# Buzzer_Circuit.net
KiCad netlist of a schematic drawn in Altium Designer
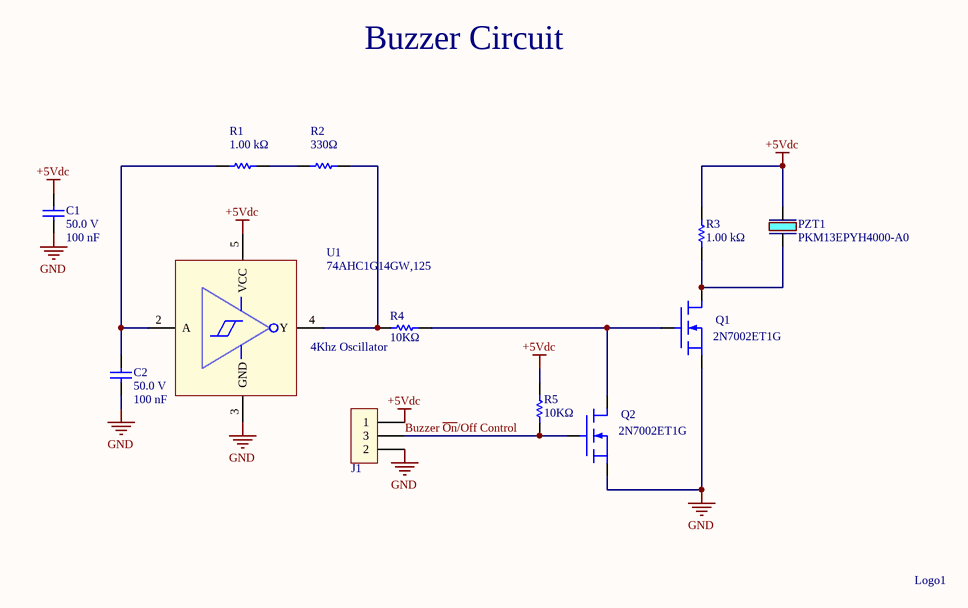
[diagram p0: Buzzer Circuit.SchDoc]

(export (version "E")
  (design (tool "Eeschema 10.0.6"))
  (components
    (comp (ref "C1")
      (value "08055C104JAT2A")
      (footprint "Cap,0805")
      (description "Capacitor; Ceramic; Cap 0.1 uF; Tol 5%; Vol-Rtg 50 VDC; SMT; 0805; X7R; Tape & Reel")
      (fields (field (name "VOLTAGE RATING (DC)") "50.0 V") (field (name "CAPACITANCE") "100 nF"))
      (libsource (lib "Master Mar2021") (part "Cap,0805,100nf,50V,5%,08055C104JAT2A"))
    )
    (comp (ref "C2")
      (value "08055C104JAT2A")
      (footprint "Cap,0805")
      (description "Capacitor; Ceramic; Cap 0.1 uF; Tol 5%; Vol-Rtg 50 VDC; SMT; 0805; X7R; Tape & Reel")
      (fields (field (name "VOLTAGE RATING (DC)") "50.0 V") (field (name "CAPACITANCE") "100 nF"))
      (libsource (lib "Master Mar2021") (part "Cap,0805,100nf,50V,5%,08055C104JAT2A"))
    )
    (comp (ref "J1")
      (value "Generic Header")
      (footprint "Header,3POS,0.1\",RA")
      (description "Generic Header 3 pos header 0.1\"")
      (libsource (lib "Master DEC 2020") (part "Header 1x3,0.1{dblquote},TH,Generic"))
    )
    (comp (ref "Logo1")
      (value "Open Source Logo")
      (footprint "Symbol,Open Source")
      (description "Open Source Silk Screen Logo")
      (libsource (lib "Master Mar2024") (part "Symbol,Open Source"))
    )
    (comp (ref "PZT1")
      (value "PKM13EPYH4000-A0")
      (footprint "Buzzer,PKM13EPYH4000-A0")
      (description "AUDIO PIEZO TRANSDUCER 30V TH")
      (fields (field (name "MANUFACTURER") "Murata Electronics"))
      (libsource (lib "Master Mar2021") (part "Buzzer,PIEZO,30V,TH,4Khz,PKM13EPYH4000-A0"))
    )
    (comp (ref "Q1")
      (value "2N7002ET1G")
      (footprint "SOT23-3")
      (description "Small Signal MOSFET, 60 V, 310 mA, Single, N-Channel, 3-Pin SOT-23, Pb-Free, Tape and Reel")
      (fields
        (field (name "MANUFACTURER") "ON Semiconductor")
        (field (name "MANUFACTURER PART NUMBER") "2N7002ET1G")
      )
      (libsource (lib "Master Mar2021") (part "MOSFET,N-Channel,SOT23,0.25A,60V,2N7002ET1G"))
    )
    (comp (ref "Q2")
      (value "2N7002ET1G")
      (footprint "SOT23-3")
      (description "Small Signal MOSFET, 60 V, 310 mA, Single, N-Channel, 3-Pin SOT-23, Pb-Free, Tape and Reel")
      (fields
        (field (name "MANUFACTURER") "ON Semiconductor")
        (field (name "MANUFACTURER PART NUMBER") "2N7002ET1G")
      )
      (libsource (lib "Master Mar2021") (part "MOSFET,N-Channel,SOT23,0.25A,60V,2N7002ET1G"))
    )
    (comp (ref "R1")
      (value "Vishay CRCW08051K00JNEA")
      (footprint "res, 0805, HD")
      (description "Res Thick Film 0805 1K Ohm 5% 0.125W(1/8W) ±200ppm/C Molded SMD Automotive Paper T/R")
      (fields
        (field (name "MANUFACTURER PART NUMBER") "CRCW08051K00JNEA")
        (field (name "RESISTANCE") "1.00 kΩ")
      )
      (libsource (lib "Master Mar2021") (part "Res,0805,1.00 kΩ,5%,200ppm,CRCW08051K00JNEA"))
    )
    (comp (ref "R2")
      (value "Res1")
      (footprint "res, 0805, HD")
      (fields (field (name "RESISTANCE") "330Ω"))
      (libsource (lib "Master Nov2021") (part "Res,0805,Generic"))
    )
    (comp (ref "R3")
      (value "Vishay CRCW08051K00JNEA")
      (footprint "res, 0805, HD")
      (description "Res Thick Film 0805 1K Ohm 5% 0.125W(1/8W) ±200ppm/C Molded SMD Automotive Paper T/R")
      (fields
        (field (name "MANUFACTURER PART NUMBER") "CRCW08051K00JNEA")
        (field (name "RESISTANCE") "1.00 kΩ")
      )
      (libsource (lib "Master Mar2021") (part "Res,0805,1.00 kΩ,5%,200ppm,CRCW08051K00JNEA"))
    )
    (comp (ref "R4")
      (value "Vishay / Dale CRCW080510K0FKTA")
      (footprint "res, 0805, HD")
      (description "RES SMD 10K OHM 1% 1/8W 0805")
      (fields (field (name "RESISTANCE") "10KΩ"))
      (libsource (lib "Master Mar2021") (part "Res,0805,10.0kΩ,1%,100 ppm,CRCW080510K0FKTA"))
    )
    (comp (ref "R5")
      (value "Vishay / Dale CRCW080510K0FKTA")
      (footprint "res, 0805, HD")
      (description "RES SMD 10K OHM 1% 1/8W 0805")
      (fields (field (name "RESISTANCE") "10KΩ"))
      (libsource (lib "Master Mar2021") (part "Res,0805,10.0kΩ,1%,100 ppm,CRCW080510K0FKTA"))
    )
    (comp (ref "U1")
      (value "74AHC1G14GW,125")
      (footprint "SOT-353")
      (description "IC INVERTER SCHMITT 1CH 5TSSOP")
      (fields (field (name "MANUFACTURER") "Nexperia USA Inc."))
      (libsource (lib "Master Nov2021") (part "IC,Logic,Schmitt trigger INV,2V ~ 5.5V,5-TSSOP , 74AHC1G14GW,125"))
    )
  )
  (nets
    (net (code "1") (name "+5Vdc") (class "Default")
      (node (ref "C1") (pin "2") (pinfunction "2_2") (pintype "passive"))
      (node (ref "J1") (pin "1") (pinfunction "1_1") (pintype "passive"))
      (node (ref "PZT1") (pin "2") (pinfunction "2_2") (pintype "passive"))
      (node (ref "R3") (pin "1") (pinfunction "1_1") (pintype "passive"))
      (node (ref "R5") (pin "1") (pinfunction "1_1") (pintype "passive"))
      (node (ref "U1") (pin "5") (pinfunction "VCC_5") (pintype "passive"))
    )
    (net (code "2") (name "/Buzzer ~{On}{slash}Off Control") (class "Default")
      (node (ref "J1") (pin "3") (pinfunction "3_3") (pintype "passive"))
      (node (ref "Q2") (pin "1") (pinfunction "G_1") (pintype "passive"))
      (node (ref "R5") (pin "2") (pinfunction "2_2") (pintype "passive"))
    )
    (net (code "3") (name "GND") (class "Default")
      (node (ref "C1") (pin "1") (pinfunction "1_1") (pintype "passive"))
      (node (ref "C2") (pin "2") (pinfunction "2_2") (pintype "passive"))
      (node (ref "J1") (pin "2") (pinfunction "2_2") (pintype "passive"))
      (node (ref "Q1") (pin "2") (pinfunction "S_2") (pintype "passive"))
      (node (ref "Q2") (pin "2") (pinfunction "S_2") (pintype "passive"))
      (node (ref "U1") (pin "3") (pinfunction "GND_3") (pintype "passive"))
    )
    (net (code "4") (name "Net-(Q1-D)") (class "Default")
      (node (ref "PZT1") (pin "1") (pinfunction "1_1") (pintype "passive"))
      (node (ref "Q1") (pin "3") (pinfunction "D_3") (pintype "passive"))
      (node (ref "R3") (pin "2") (pinfunction "2_2") (pintype "passive"))
    )
    (net (code "5") (name "Net-(Q1-G)") (class "Default")
      (node (ref "Q1") (pin "1") (pinfunction "G_1") (pintype "passive"))
      (node (ref "Q2") (pin "3") (pinfunction "D_3") (pintype "passive"))
      (node (ref "R4") (pin "1") (pinfunction "1_1") (pintype "passive"))
    )
    (net (code "6") (name "Net-(R1-Pad2)") (class "Default")
      (node (ref "R1") (pin "2") (pinfunction "2_2") (pintype "passive"))
      (node (ref "R2") (pin "2") (pinfunction "2_2") (pintype "passive"))
    )
    (net (code "7") (name "Net-(U1-A)") (class "Default")
      (node (ref "C2") (pin "1") (pinfunction "1_1") (pintype "passive"))
      (node (ref "R1") (pin "1") (pinfunction "1_1") (pintype "passive"))
      (node (ref "U1") (pin "2") (pinfunction "A_2") (pintype "passive"))
    )
    (net (code "8") (name "Net-(U1-Y)") (class "Default")
      (node (ref "R2") (pin "1") (pinfunction "1_1") (pintype "passive"))
      (node (ref "R4") (pin "2") (pinfunction "2_2") (pintype "passive"))
      (node (ref "U1") (pin "4") (pinfunction "Y_4") (pintype "passive"))
    )
    (net (code "9") (name "unconnected-(U1-N{slash}C-Pad1)") (class "Default")
      (node (ref "U1") (pin "1") (pinfunction "N/C_1") (pintype "passive"))
    )
  )
)
